# sensors.net
KiCad netlist of a schematic drawn in EAGLE
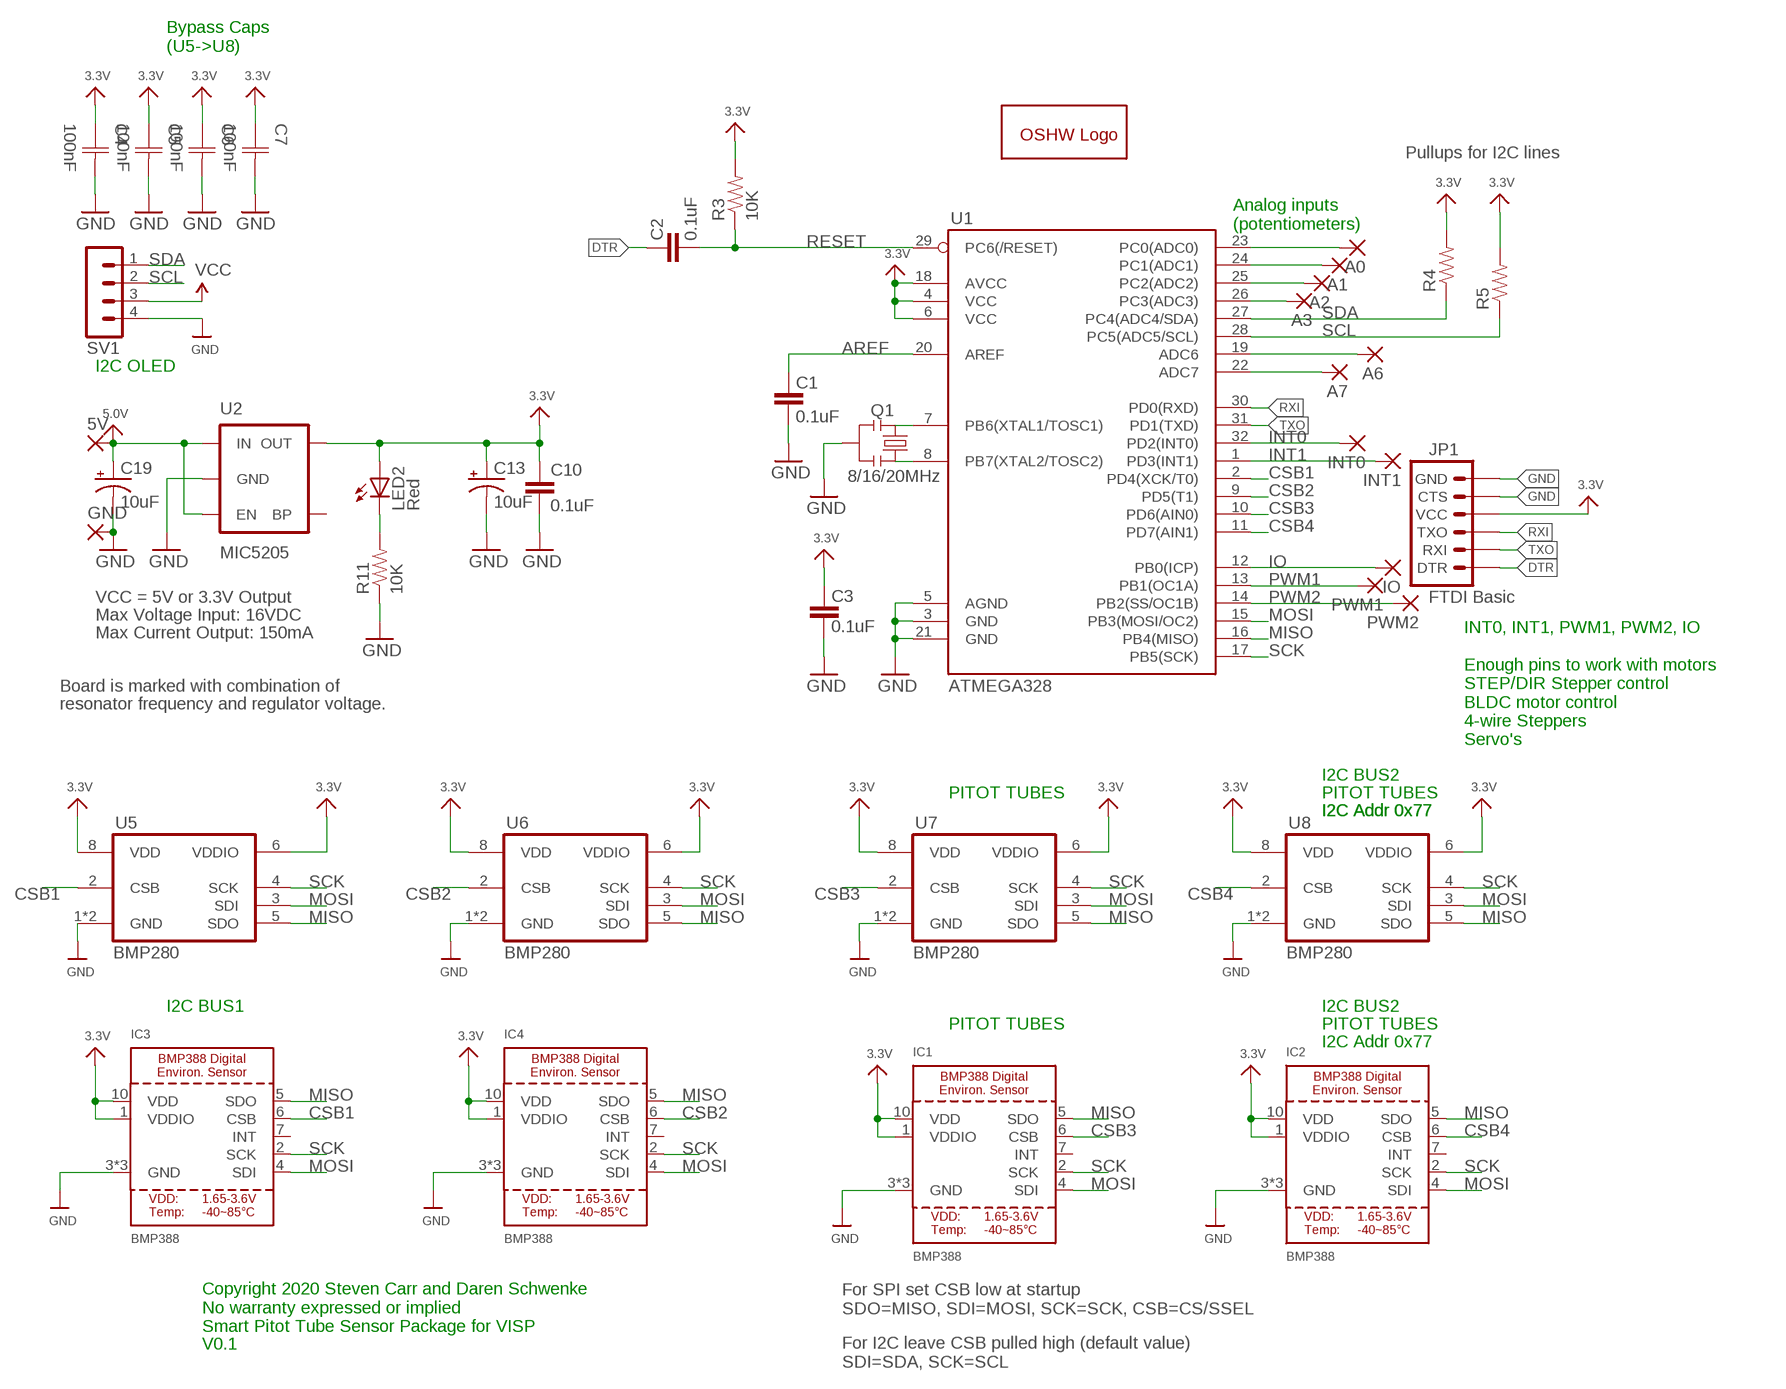
[diagram p0: schematic, sheet 1]

(export (version "E")
  (design (tool "Eeschema 10.0.6"))
  (components
    (comp (ref "5V")
      (value "SMD2")
      (footprint "eagle-import:SMD1,27-2,54")
      (libsource (lib "eagle-import") (part "SMD2"))
    )
    (comp (ref "A0")
      (value "SMD2")
      (footprint "eagle-import:SMD1,27-2,54")
      (libsource (lib "eagle-import") (part "SMD2"))
    )
    (comp (ref "A1")
      (value "SMD2")
      (footprint "eagle-import:SMD1,27-2,54")
      (libsource (lib "eagle-import") (part "SMD2"))
    )
    (comp (ref "A2")
      (value "SMD2")
      (footprint "eagle-import:SMD1,27-2,54")
      (libsource (lib "eagle-import") (part "SMD2"))
    )
    (comp (ref "A3")
      (value "SMD2")
      (footprint "eagle-import:SMD1,27-2,54")
      (libsource (lib "eagle-import") (part "SMD2"))
    )
    (comp (ref "A6")
      (value "SMD2")
      (footprint "eagle-import:SMD1,27-2,54")
      (libsource (lib "eagle-import") (part "SMD2"))
    )
    (comp (ref "A7")
      (value "SMD2")
      (footprint "eagle-import:SMD1,27-2,54")
      (libsource (lib "eagle-import") (part "SMD2"))
    )
    (comp (ref "C1")
      (value "0.1uF")
      (footprint "eagle-import:0603-CAP")
      (libsource (lib "eagle-import") (part "CAP0603-CAP"))
    )
    (comp (ref "C2")
      (value "0.1uF")
      (footprint "eagle-import:0603-CAP")
      (libsource (lib "eagle-import") (part "CAP0603-CAP"))
    )
    (comp (ref "C3")
      (value "0.1uF")
      (footprint "eagle-import:0603-CAP")
      (libsource (lib "eagle-import") (part "CAP0603-CAP"))
    )
    (comp (ref "C4")
      (value "100nF")
      (footprint "eagle-import:CAP0402")
      (fields (field (name "MPN") " CL10F104ZO8NNNC "))
      (libsource (lib "eagle-import") (part "CAPACITOR-0402"))
    )
    (comp (ref "C5")
      (value "100nF")
      (footprint "eagle-import:CAP0402")
      (fields (field (name "MPN") " CL10F104ZO8NNNC "))
      (libsource (lib "eagle-import") (part "CAPACITOR-0402"))
    )
    (comp (ref "C6")
      (value "100nF")
      (footprint "eagle-import:CAP0402")
      (fields (field (name "MPN") " CL10F104ZO8NNNC "))
      (libsource (lib "eagle-import") (part "CAPACITOR-0402"))
    )
    (comp (ref "C7")
      (value "100nF")
      (footprint "eagle-import:CAP0402")
      (fields (field (name "MPN") " CL10F104ZO8NNNC "))
      (libsource (lib "eagle-import") (part "CAPACITOR-0402"))
    )
    (comp (ref "C10")
      (value "0.1uF")
      (footprint "eagle-import:0603-CAP")
      (libsource (lib "eagle-import") (part "CAP0603-CAP"))
    )
    (comp (ref "C13")
      (value "10uF")
      (footprint "eagle-import:EIA3216")
      (libsource (lib "eagle-import") (part "CAP_POL1206"))
    )
    (comp (ref "C19")
      (value "10uF")
      (footprint "eagle-import:EIA3216")
      (libsource (lib "eagle-import") (part "CAP_POL1206"))
    )
    (comp (ref "GND")
      (value "SMD2")
      (footprint "eagle-import:SMD1,27-2,54")
      (libsource (lib "eagle-import") (part "SMD2"))
    )
    (comp (ref "GOLD_ORB_SM1")
      (value "OSHWLOGOLOGO8MM")
      (footprint "eagle-import:OSHW_8MM")
      (libsource (lib "eagle-import") (part "OSHWLOGOLOGO8MM"))
    )
    (comp (ref "IC1")
      (value "BMP388")
      (footprint "eagle-import:BMP388")
      (libsource (lib "eagle-import") (part "BMP388"))
    )
    (comp (ref "IC2")
      (value "BMP388")
      (footprint "eagle-import:BMP388")
      (libsource (lib "eagle-import") (part "BMP388"))
    )
    (comp (ref "IC3")
      (value "BMP388")
      (footprint "eagle-import:BMP388")
      (libsource (lib "eagle-import") (part "BMP388"))
    )
    (comp (ref "IC4")
      (value "BMP388")
      (footprint "eagle-import:BMP388")
      (libsource (lib "eagle-import") (part "BMP388"))
    )
    (comp (ref "INT0")
      (value "SMD2")
      (footprint "eagle-import:SMD1,27-2,54")
      (libsource (lib "eagle-import") (part "SMD2"))
    )
    (comp (ref "INT1")
      (value "SMD2")
      (footprint "eagle-import:SMD1,27-2,54")
      (libsource (lib "eagle-import") (part "SMD2"))
    )
    (comp (ref "IO")
      (value "SMD2")
      (footprint "eagle-import:SMD1,27-2,54")
      (libsource (lib "eagle-import") (part "SMD2"))
    )
    (comp (ref "JP1")
      (value "FTDI Basic")
      (footprint "eagle-import:1X06")
      (libsource (lib "eagle-import") (part "ARDUINO_SERIAL_PROGRAMPTH"))
    )
    (comp (ref "LED2")
      (value "Red")
      (footprint "eagle-import:0603-LED-ALT1")
      (libsource (lib "eagle-import") (part "LED"))
    )
    (comp (ref "PWM1")
      (value "SMD2")
      (footprint "eagle-import:SMD1,27-2,54")
      (libsource (lib "eagle-import") (part "SMD2"))
    )
    (comp (ref "PWM2")
      (value "SMD2")
      (footprint "eagle-import:SMD1,27-2,54")
      (libsource (lib "eagle-import") (part "SMD2"))
    )
    (comp (ref "Q1")
      (value "8/16/20MHz")
      (footprint "eagle-import:RESONATOR-SMD-1_1")
      (libsource (lib "eagle-import") (part "RESONATOR1{colon}1"))
    )
    (comp (ref "R3")
      (value "10K")
      (footprint "eagle-import:0603-RES")
      (libsource (lib "eagle-import") (part "RESISTOR0603-RES"))
    )
    (comp (ref "R4")
      (value "RESISTOR0603-RES")
      (footprint "eagle-import:0603-RES")
      (libsource (lib "eagle-import") (part "RESISTOR0603-RES"))
    )
    (comp (ref "R5")
      (value "RESISTOR0603-RES")
      (footprint "eagle-import:0603-RES")
      (libsource (lib "eagle-import") (part "RESISTOR0603-RES"))
    )
    (comp (ref "R11")
      (value "10K")
      (footprint "eagle-import:0603-RES")
      (libsource (lib "eagle-import") (part "RESISTOR0603-RES"))
    )
    (comp (ref "SV1")
      (value "MA04-1")
      (footprint "eagle-import:MA04-1")
      (libsource (lib "eagle-import") (part "MA04-1"))
    )
    (comp (ref "U1")
      (value "ATMEGA328")
      (footprint "eagle-import:TQFP32-08")
      (libsource (lib "eagle-import") (part "ATMEGA168"))
    )
    (comp (ref "U2")
      (value "MIC5205")
      (footprint "eagle-import:SOT23-5")
      (libsource (lib "eagle-import") (part "V_REG_LDOSMD"))
    )
    (comp (ref "U5")
      (value "BMP280")
      (footprint "eagle-import:BMP280")
      (libsource (lib "eagle-import") (part "BMP280"))
    )
    (comp (ref "U6")
      (value "BMP280")
      (footprint "eagle-import:BMP280")
      (libsource (lib "eagle-import") (part "BMP280"))
    )
    (comp (ref "U7")
      (value "BMP280")
      (footprint "eagle-import:BMP280")
      (libsource (lib "eagle-import") (part "BMP280"))
    )
    (comp (ref "U8")
      (value "BMP280")
      (footprint "eagle-import:BMP280")
      (libsource (lib "eagle-import") (part "BMP280"))
    )
  )
  (nets
    (net (code "1") (name "/AREF") (class "Default")
      (node (ref "C1") (pin "2") (pinfunction "2_2") (pintype "passive"))
      (node (ref "U1") (pin "20") (pinfunction "AREF_20") (pintype "bidirectional"))
    )
    (net (code "2") (name "/CSB1") (class "Default")
      (node (ref "IC3") (pin "6") (pinfunction "CSB_6") (pintype "input"))
      (node (ref "U1") (pin "2") (pinfunction "PD4(XCK/T0)_2") (pintype "bidirectional"))
      (node (ref "U5") (pin "2") (pinfunction "CSB_2") (pintype "input"))
    )
    (net (code "3") (name "/CSB2") (class "Default")
      (node (ref "IC4") (pin "6") (pinfunction "CSB_6") (pintype "input"))
      (node (ref "U1") (pin "9") (pinfunction "PD5(T1)_9") (pintype "bidirectional"))
      (node (ref "U6") (pin "2") (pinfunction "CSB_2") (pintype "input"))
    )
    (net (code "4") (name "/CSB3") (class "Default")
      (node (ref "IC1") (pin "6") (pinfunction "CSB_6") (pintype "input"))
      (node (ref "U1") (pin "10") (pinfunction "PD6(AIN0)_10") (pintype "bidirectional"))
      (node (ref "U7") (pin "2") (pinfunction "CSB_2") (pintype "input"))
    )
    (net (code "5") (name "/CSB4") (class "Default")
      (node (ref "IC2") (pin "6") (pinfunction "CSB_6") (pintype "input"))
      (node (ref "U1") (pin "11") (pinfunction "PD7(AIN1)_11") (pintype "bidirectional"))
      (node (ref "U8") (pin "2") (pinfunction "CSB_2") (pintype "input"))
    )
    (net (code "6") (name "/INT0") (class "Default")
      (node (ref "INT0") (pin "1") (pinfunction "P_1") (pintype "passive"))
      (node (ref "U1") (pin "32") (pinfunction "PD2(INT0)_32") (pintype "bidirectional"))
    )
    (net (code "7") (name "/INT1") (class "Default")
      (node (ref "INT1") (pin "1") (pinfunction "P_1") (pintype "passive"))
      (node (ref "U1") (pin "1") (pinfunction "PD3(INT1)_1") (pintype "bidirectional"))
    )
    (net (code "8") (name "/IO") (class "Default")
      (node (ref "IO") (pin "1") (pinfunction "P_1") (pintype "passive"))
      (node (ref "U1") (pin "12") (pinfunction "PB0(ICP)_12") (pintype "bidirectional"))
    )
    (net (code "9") (name "/MISO") (class "Default")
      (node (ref "IC1") (pin "5") (pinfunction "SDO_5") (pintype "output"))
      (node (ref "IC2") (pin "5") (pinfunction "SDO_5") (pintype "output"))
      (node (ref "IC3") (pin "5") (pinfunction "SDO_5") (pintype "output"))
      (node (ref "IC4") (pin "5") (pinfunction "SDO_5") (pintype "output"))
      (node (ref "U1") (pin "16") (pinfunction "PB4(MISO)_16") (pintype "bidirectional"))
      (node (ref "U5") (pin "5") (pinfunction "SDO_5") (pintype "input"))
      (node (ref "U6") (pin "5") (pinfunction "SDO_5") (pintype "input"))
      (node (ref "U7") (pin "5") (pinfunction "SDO_5") (pintype "input"))
      (node (ref "U8") (pin "5") (pinfunction "SDO_5") (pintype "input"))
    )
    (net (code "10") (name "/MOSI") (class "Default")
      (node (ref "IC1") (pin "4") (pinfunction "SDI_4") (pintype "input"))
      (node (ref "IC2") (pin "4") (pinfunction "SDI_4") (pintype "input"))
      (node (ref "IC3") (pin "4") (pinfunction "SDI_4") (pintype "input"))
      (node (ref "IC4") (pin "4") (pinfunction "SDI_4") (pintype "input"))
      (node (ref "U1") (pin "15") (pinfunction "PB3(MOSI/OC2)_15") (pintype "bidirectional"))
      (node (ref "U5") (pin "3") (pinfunction "SDI_3") (pintype "bidirectional"))
      (node (ref "U6") (pin "3") (pinfunction "SDI_3") (pintype "bidirectional"))
      (node (ref "U7") (pin "3") (pinfunction "SDI_3") (pintype "bidirectional"))
      (node (ref "U8") (pin "3") (pinfunction "SDI_3") (pintype "bidirectional"))
    )
    (net (code "11") (name "/PWM1") (class "Default")
      (node (ref "PWM1") (pin "1") (pinfunction "P_1") (pintype "passive"))
      (node (ref "U1") (pin "13") (pinfunction "PB1(OC1A)_13") (pintype "bidirectional"))
    )
    (net (code "12") (name "/PWM2") (class "Default")
      (node (ref "PWM2") (pin "1") (pinfunction "P_1") (pintype "passive"))
      (node (ref "U1") (pin "14") (pinfunction "PB2(SS/OC1B)_14") (pintype "bidirectional"))
    )
    (net (code "13") (name "/RESET") (class "Default")
      (node (ref "C2") (pin "1") (pinfunction "1_1") (pintype "passive"))
      (node (ref "R3") (pin "1") (pinfunction "1_1") (pintype "passive"))
      (node (ref "U1") (pin "29") (pinfunction "PC6(/RESET)_29") (pintype "bidirectional"))
    )
    (net (code "14") (name "/SCK") (class "Default")
      (node (ref "IC1") (pin "2") (pinfunction "SCK_2") (pintype "input"))
      (node (ref "IC2") (pin "2") (pinfunction "SCK_2") (pintype "input"))
      (node (ref "IC3") (pin "2") (pinfunction "SCK_2") (pintype "input"))
      (node (ref "IC4") (pin "2") (pinfunction "SCK_2") (pintype "input"))
      (node (ref "U1") (pin "17") (pinfunction "PB5(SCK)_17") (pintype "bidirectional"))
      (node (ref "U5") (pin "4") (pinfunction "SCK_4") (pintype "bidirectional"))
      (node (ref "U6") (pin "4") (pinfunction "SCK_4") (pintype "bidirectional"))
      (node (ref "U7") (pin "4") (pinfunction "SCK_4") (pintype "bidirectional"))
      (node (ref "U8") (pin "4") (pinfunction "SCK_4") (pintype "bidirectional"))
    )
    (net (code "15") (name "/SCL") (class "Default")
      (node (ref "R5") (pin "1") (pinfunction "1_1") (pintype "passive"))
      (node (ref "SV1") (pin "2") (pinfunction "2_2") (pintype "passive"))
      (node (ref "U1") (pin "28") (pinfunction "PC5(ADC5/SCL)_28") (pintype "bidirectional"))
    )
    (net (code "16") (name "/SDA") (class "Default")
      (node (ref "R4") (pin "1") (pinfunction "1_1") (pintype "passive"))
      (node (ref "SV1") (pin "1") (pinfunction "1_1") (pintype "passive"))
      (node (ref "U1") (pin "27") (pinfunction "PC4(ADC4/SDA)_27") (pintype "bidirectional"))
    )
    (net (code "17") (name "3.3V") (class "Default")
      (node (ref "C10") (pin "1") (pinfunction "1_1") (pintype "passive"))
      (node (ref "C13") (pin "A") (pinfunction "+_A") (pintype "passive"))
      (node (ref "C3") (pin "2") (pinfunction "2_2") (pintype "passive"))
      (node (ref "C4") (pin "1") (pinfunction "C1_1") (pintype "passive"))
      (node (ref "C5") (pin "1") (pinfunction "C1_1") (pintype "passive"))
      (node (ref "C6") (pin "1") (pinfunction "C1_1") (pintype "passive"))
      (node (ref "C7") (pin "1") (pinfunction "C1_1") (pintype "passive"))
      (node (ref "IC1") (pin "1") (pinfunction "VDDIO_1") (pintype "power_in"))
      (node (ref "IC1") (pin "10") (pinfunction "VDD_10") (pintype "power_in"))
      (node (ref "IC2") (pin "1") (pinfunction "VDDIO_1") (pintype "power_in"))
      (node (ref "IC2") (pin "10") (pinfunction "VDD_10") (pintype "power_in"))
      (node (ref "IC3") (pin "1") (pinfunction "VDDIO_1") (pintype "power_in"))
      (node (ref "IC3") (pin "10") (pinfunction "VDD_10") (pintype "power_in"))
      (node (ref "IC4") (pin "1") (pinfunction "VDDIO_1") (pintype "power_in"))
      (node (ref "IC4") (pin "10") (pinfunction "VDD_10") (pintype "power_in"))
      (node (ref "JP1") (pin "4") (pinfunction "VCC_4") (pintype "passive"))
      (node (ref "LED2") (pin "A") (pinfunction "A_A") (pintype "passive"))
      (node (ref "R3") (pin "2") (pinfunction "2_2") (pintype "passive"))
      (node (ref "R4") (pin "2") (pinfunction "2_2") (pintype "passive"))
      (node (ref "R5") (pin "2") (pinfunction "2_2") (pintype "passive"))
      (node (ref "SV1") (pin "3") (pinfunction "3_3") (pintype "passive"))
      (node (ref "U1") (pin "18") (pinfunction "AVCC_18") (pintype "bidirectional"))
      (node (ref "U1") (pin "4") (pinfunction "VCC_4") (pintype "bidirectional"))
      (node (ref "U1") (pin "6") (pinfunction "VCC_6") (pintype "bidirectional"))
      (node (ref "U2") (pin "5") (pinfunction "OUT_5") (pintype "passive"))
      (node (ref "U5") (pin "6") (pinfunction "VDDIO_6") (pintype "power_in"))
      (node (ref "U5") (pin "8") (pinfunction "VDD_8") (pintype "power_in"))
      (node (ref "U6") (pin "6") (pinfunction "VDDIO_6") (pintype "power_in"))
      (node (ref "U6") (pin "8") (pinfunction "VDD_8") (pintype "power_in"))
      (node (ref "U7") (pin "6") (pinfunction "VDDIO_6") (pintype "power_in"))
      (node (ref "U7") (pin "8") (pinfunction "VDD_8") (pintype "power_in"))
      (node (ref "U8") (pin "6") (pinfunction "VDDIO_6") (pintype "power_in"))
      (node (ref "U8") (pin "8") (pinfunction "VDD_8") (pintype "power_in"))
    )
    (net (code "18") (name "5.0V") (class "Default")
      (node (ref "5V") (pin "1") (pinfunction "P_1") (pintype "passive"))
      (node (ref "C19") (pin "A") (pinfunction "+_A") (pintype "passive"))
      (node (ref "U2") (pin "1") (pinfunction "IN_1") (pintype "input"))
      (node (ref "U2") (pin "3") (pinfunction "EN_3") (pintype "input"))
    )
    (net (code "19") (name "DTR") (class "Default")
      (node (ref "C2") (pin "2") (pinfunction "2_2") (pintype "passive"))
      (node (ref "JP1") (pin "1") (pinfunction "DTR_1") (pintype "passive"))
    )
    (net (code "20") (name "GND") (class "Default")
      (node (ref "C1") (pin "1") (pinfunction "1_1") (pintype "passive"))
      (node (ref "C10") (pin "2") (pinfunction "2_2") (pintype "passive"))
      (node (ref "C13") (pin "C") (pinfunction "-_C") (pintype "passive"))
      (node (ref "C19") (pin "C") (pinfunction "-_C") (pintype "passive"))
      (node (ref "C3") (pin "1") (pinfunction "1_1") (pintype "passive"))
      (node (ref "C4") (pin "2") (pinfunction "C2_2") (pintype "passive"))
      (node (ref "C5") (pin "2") (pinfunction "C2_2") (pintype "passive"))
      (node (ref "C6") (pin "2") (pinfunction "C2_2") (pintype "passive"))
      (node (ref "C7") (pin "2") (pinfunction "C2_2") (pintype "passive"))
      (node (ref "GND") (pin "1") (pinfunction "P_1") (pintype "passive"))
      (node (ref "IC1") (pin "3") (pinfunction "GND_3") (pintype "power_in"))
      (node (ref "IC1") (pin "8") (pinfunction "GND_8") (pintype "power_in"))
      (node (ref "IC1") (pin "9") (pinfunction "GND_9") (pintype "power_in"))
      (node (ref "IC2") (pin "3") (pinfunction "GND_3") (pintype "power_in"))
      (node (ref "IC2") (pin "8") (pinfunction "GND_8") (pintype "power_in"))
      (node (ref "IC2") (pin "9") (pinfunction "GND_9") (pintype "power_in"))
      (node (ref "IC3") (pin "3") (pinfunction "GND_3") (pintype "power_in"))
      (node (ref "IC3") (pin "8") (pinfunction "GND_8") (pintype "power_in"))
      (node (ref "IC3") (pin "9") (pinfunction "GND_9") (pintype "power_in"))
      (node (ref "IC4") (pin "3") (pinfunction "GND_3") (pintype "power_in"))
      (node (ref "IC4") (pin "8") (pinfunction "GND_8") (pintype "power_in"))
      (node (ref "IC4") (pin "9") (pinfunction "GND_9") (pintype "power_in"))
      (node (ref "JP1") (pin "5") (pinfunction "CTS_5") (pintype "passive"))
      (node (ref "JP1") (pin "6") (pinfunction "GND_6") (pintype "passive"))
      (node (ref "Q1") (pin "2") (pinfunction "2_2") (pintype "passive"))
      (node (ref "R11") (pin "1") (pinfunction "1_1") (pintype "passive"))
      (node (ref "SV1") (pin "4") (pinfunction "4_4") (pintype "passive"))
      (node (ref "U1") (pin "21") (pinfunction "GND_21") (pintype "bidirectional"))
      (node (ref "U1") (pin "3") (pinfunction "GND_3") (pintype "bidirectional"))
      (node (ref "U1") (pin "5") (pinfunction "AGND_5") (pintype "bidirectional"))
      (node (ref "U2") (pin "2") (pinfunction "GND_2") (pintype "input"))
      (node (ref "U5") (pin "1") (pinfunction "GND_1") (pintype "power_in"))
      (node (ref "U5") (pin "7") (pinfunction "GND_7") (pintype "power_in"))
      (node (ref "U6") (pin "1") (pinfunction "GND_1") (pintype "power_in"))
      (node (ref "U6") (pin "7") (pinfunction "GND_7") (pintype "power_in"))
      (node (ref "U7") (pin "1") (pinfunction "GND_1") (pintype "power_in"))
      (node (ref "U7") (pin "7") (pinfunction "GND_7") (pintype "power_in"))
      (node (ref "U8") (pin "1") (pinfunction "GND_1") (pintype "power_in"))
      (node (ref "U8") (pin "7") (pinfunction "GND_7") (pintype "power_in"))
    )
    (net (code "21") (name "Net-(A0-P)") (class "Default")
      (node (ref "A0") (pin "1") (pinfunction "P_1") (pintype "passive"))
      (node (ref "U1") (pin "23") (pinfunction "PC0(ADC0)_23") (pintype "bidirectional"))
    )
    (net (code "22") (name "Net-(A1-P)") (class "Default")
      (node (ref "A1") (pin "1") (pinfunction "P_1") (pintype "passive"))
      (node (ref "U1") (pin "24") (pinfunction "PC1(ADC1)_24") (pintype "bidirectional"))
    )
    (net (code "23") (name "Net-(A2-P)") (class "Default")
      (node (ref "A2") (pin "1") (pinfunction "P_1") (pintype "passive"))
      (node (ref "U1") (pin "25") (pinfunction "PC2(ADC2)_25") (pintype "bidirectional"))
    )
    (net (code "24") (name "Net-(A3-P)") (class "Default")
      (node (ref "A3") (pin "1") (pinfunction "P_1") (pintype "passive"))
      (node (ref "U1") (pin "26") (pinfunction "PC3(ADC3)_26") (pintype "bidirectional"))
    )
    (net (code "25") (name "Net-(A6-P)") (class "Default")
      (node (ref "A6") (pin "1") (pinfunction "P_1") (pintype "passive"))
      (node (ref "U1") (pin "19") (pinfunction "ADC6_19") (pintype "bidirectional"))
    )
    (net (code "26") (name "Net-(A7-P)") (class "Default")
      (node (ref "A7") (pin "1") (pinfunction "P_1") (pintype "passive"))
      (node (ref "U1") (pin "22") (pinfunction "ADC7_22") (pintype "bidirectional"))
    )
    (net (code "27") (name "Net-(LED2-PadC)") (class "Default")
      (node (ref "LED2") (pin "C") (pinfunction "C_C") (pintype "passive"))
      (node (ref "R11") (pin "2") (pinfunction "2_2") (pintype "passive"))
    )
    (net (code "28") (name "Net-(U1-PB6(XTAL1{slash}TOSC1))") (class "Default")
      (node (ref "Q1") (pin "1") (pinfunction "1_1") (pintype "passive"))
      (node (ref "U1") (pin "7") (pinfunction "PB6(XTAL1/TOSC1)_7") (pintype "bidirectional"))
    )
    (net (code "29") (name "Net-(U1-PB7(XTAL2{slash}TOSC2))") (class "Default")
      (node (ref "Q1") (pin "3") (pinfunction "3_3") (pintype "passive"))
      (node (ref "U1") (pin "8") (pinfunction "PB7(XTAL2/TOSC2)_8") (pintype "bidirectional"))
    )
    (net (code "30") (name "RXI") (class "Default")
      (node (ref "JP1") (pin "3") (pinfunction "TXO_3") (pintype "passive"))
      (node (ref "U1") (pin "30") (pinfunction "PD0(RXD)_30") (pintype "bidirectional"))
    )
    (net (code "31") (name "TXO") (class "Default")
      (node (ref "JP1") (pin "2") (pinfunction "RXI_2") (pintype "passive"))
      (node (ref "U1") (pin "31") (pinfunction "PD1(TXD)_31") (pintype "bidirectional"))
    )
    (net (code "32") (name "unconnected-(IC1-INT-Pad7)") (class "Default")
      (node (ref "IC1") (pin "7") (pinfunction "INT_7") (pintype "output"))
    )
    (net (code "33") (name "unconnected-(IC2-INT-Pad7)") (class "Default")
      (node (ref "IC2") (pin "7") (pinfunction "INT_7") (pintype "output"))
    )
    (net (code "34") (name "unconnected-(IC3-INT-Pad7)") (class "Default")
      (node (ref "IC3") (pin "7") (pinfunction "INT_7") (pintype "output"))
    )
    (net (code "35") (name "unconnected-(IC4-INT-Pad7)") (class "Default")
      (node (ref "IC4") (pin "7") (pinfunction "INT_7") (pintype "output"))
    )
    (net (code "36") (name "unconnected-(U2-BP-Pad4)") (class "Default")
      (node (ref "U2") (pin "4") (pinfunction "BP_4") (pintype "input"))
    )
  )
)
